# schematic.net
KiCad netlist of a schematic drawn in Altium Designer
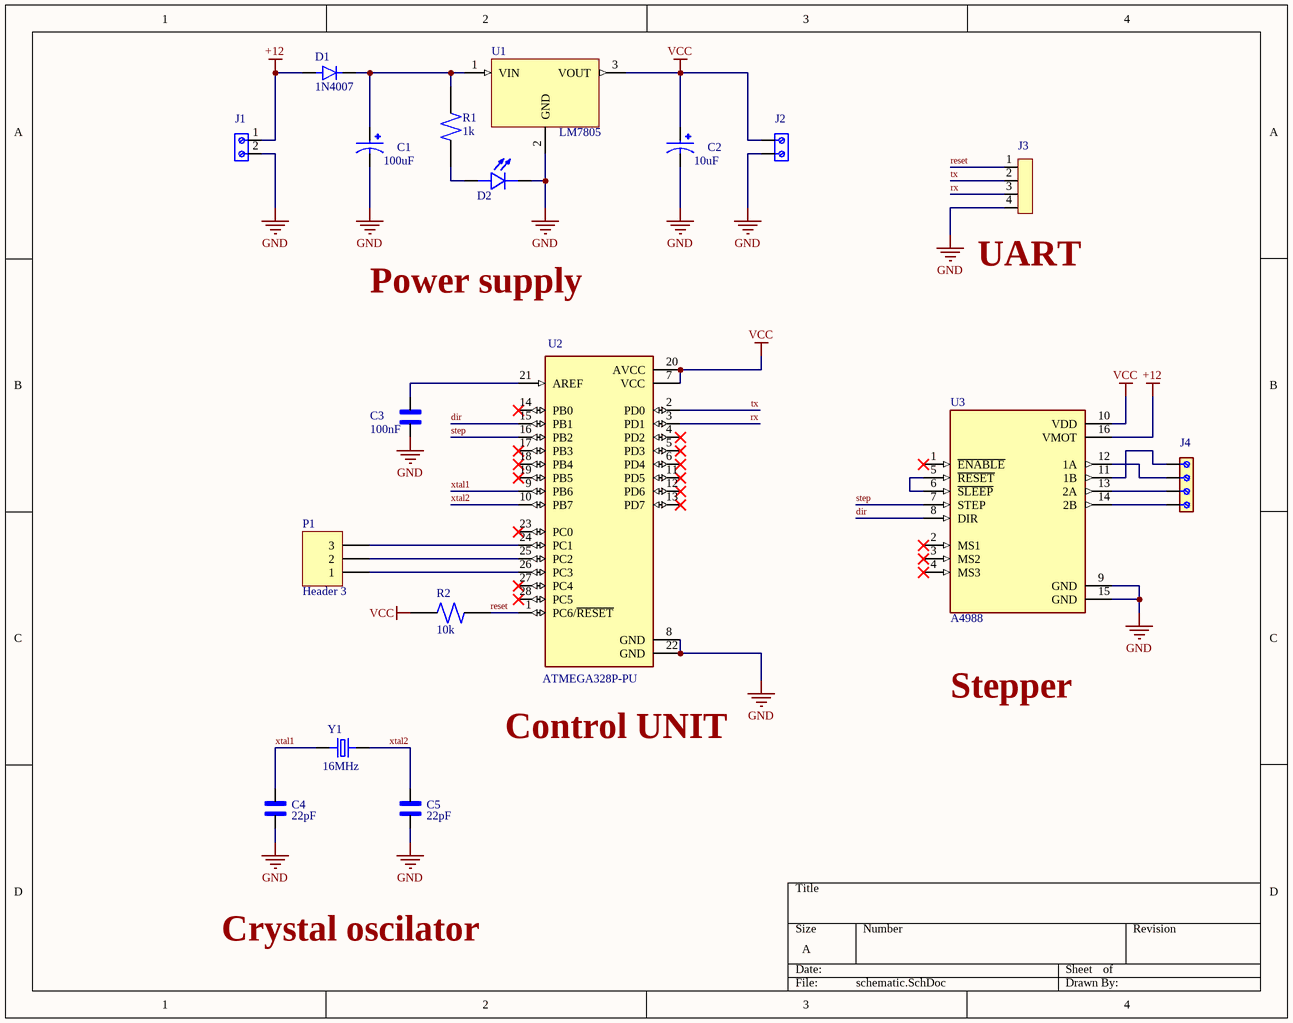
[diagram p0: schematic.SchDoc]

(export (version "E")
  (design (tool "Eeschema 10.0.6"))
  (components
    (comp (ref "C1")
      (value "100uF")
      (footprint "CAPPRD500W50D500H1100")
      (description "FS-A")
      (fields (field (name "MF") "{'manufacturer': u'Panasonic'}") (field (name "MP") "EEUFS0J221B"))
      (libsource (lib "Installed library") (part "Electrolytic capacitor"))
    )
    (comp (ref "C2")
      (value "10uF")
      (footprint "CAPPRD500W50D500H1100")
      (description "FS-A")
      (fields (field (name "MF") "{'manufacturer': u'Panasonic'}") (field (name "MP") "EEUFS0J221B"))
      (libsource (lib "Installed library") (part "Electrolytic capacitor"))
    )
    (comp (ref "C3")
      (value "100nF")
      (footprint "CAPRB500W50L450T300H550")
      (description "2200 pF Â±10% 250V Ceramic Capacitor X7R Radial")
      (fields (field (name "DIGI-KEY_PART_NUMBER") "445-173386-1-ND") (field (name "MF") "TDK"))
      (libsource (lib "Installed library") (part "Ceramic capacitor"))
    )
    (comp (ref "C4")
      (value "22pF")
      (footprint "CAPRB500W50L450T300H550")
      (description "2200 pF Â±10% 250V Ceramic Capacitor X7R Radial")
      (fields (field (name "DIGI-KEY_PART_NUMBER") "445-173386-1-ND") (field (name "MF") "TDK"))
      (libsource (lib "Installed library") (part "Ceramic capacitor"))
    )
    (comp (ref "C5")
      (value "22pF")
      (footprint "CAPRB500W50L450T300H550")
      (description "2200 pF Â±10% 250V Ceramic Capacitor X7R Radial")
      (fields (field (name "DIGI-KEY_PART_NUMBER") "445-173386-1-ND") (field (name "MF") "TDK"))
      (libsource (lib "Installed library") (part "Ceramic capacitor"))
    )
    (comp (ref "D1")
      (value "1N4007")
      (footprint "DIOAD1060W80L520D270")
      (description "Diode Switching 1KV 1A 2-Pin DO-41")
      (libsource (lib "Components") (part "1N4007"))
    )
    (comp (ref "D2")
      (value "L08R5000Q1")
      (footprint "LEDRD254W57D500H1070")
      (description "LED, Orange, Through Hole, T-1 3/4 (5mm), 30 mA, 2.1 V, 635 nm")
      (fields (field (name "MF") "{'manufacturer': u'LED Technology'}"))
      (libsource (lib "Installed library") (part "LED"))
    )
    (comp (ref "J1")
      (value "691111710002")
      (footprint "691111710002")
      (description "2 Position Wire to Board Terminal Block Horizontal with Board 0.197 _5.00mm_ Through Hole")
      (fields (field (name "MF") "Wurth Electronics"))
      (libsource (lib "Installed library") (part "Terminal Block - 2Pins"))
    )
    (comp (ref "J2")
      (value "691111710002")
      (footprint "691111710002")
      (description "2 Position Wire to Board Terminal Block Horizontal with Board 0.197 _5.00mm_ Through Hole")
      (fields (field (name "MF") "Wurth Electronics"))
      (libsource (lib "") (part "Terminal Block - 2Pins_1"))
    )
    (comp (ref "J3")
      (value "PPTC041LFBN-RC")
      (footprint "SULLINS_PPTC041LFBN-RC")
      (description "4 Position Header Connector Through Hole")
      (fields (field (name "MF") "Sullins Connector"))
      (libsource (lib "Installed library") (part "Female header - 4Pins"))
    )
    (comp (ref "J4")
      (value "691241510004")
      (footprint "691241510004")
      (fields (field (name "MF") "WÃ¼rth Elektronik"))
      (libsource (lib "Installed library") (part "Terminal block - 4Pins"))
    )
    (comp (ref "P1")
      (value "Header 3")
      (footprint "HDR1X3")
      (description "Header, 3-Pin")
      (fields (field (name "PUBLISHER") "Altium Limited"))
      (libsource (lib "Miscellaneous Connectors") (part "Header 3"))
    )
    (comp (ref "R1")
      (value "1k")
      (footprint "RESAD1100W55L680D260")
      (description "(MFR-25FBF52-10K) 10,2 kOhm bei 1% 0,25W, 1/4W Durchbohrlochwiderstand Axial Metal Film")
      (fields (field (name "DIGI-KEY_PART_NUMBER") "10.2KXBK-ND") (field (name "MF") "Yageo"))
      (libsource (lib "Installed library") (part "Resistor (0.25W)"))
    )
    (comp (ref "R2")
      (value "10k")
      (footprint "RESAD1100W55L680D260")
      (description "(MFR-25FBF52-10K) 10,2 kOhm bei 1% 0,25W, 1/4W Durchbohrlochwiderstand Axial Metal Film")
      (fields (field (name "DIGI-KEY_PART_NUMBER") "10.2KXBK-ND") (field (name "MF") "Yageo"))
      (libsource (lib "Installed library") (part "Resistor (0.25W)"))
    )
    (comp (ref "U1")
      (value "LM7805")
      (footprint "TO255P1020X450X1968-3")
      (fields (field (name "MP") "LM7805CT/NOPB"))
      (libsource (lib "Voltage regulator") (part "LM78__"))
    )
    (comp (ref "U2")
      (value "ATMEGA328P-PU")
      (footprint "DIP794W46P254L2967H457Q28B")
      (description "ATmega Series 20 MHz 32 KB Flash 2 KB SRAM 8-Bit Microcontroller - DIP-28")
      (libsource (lib "Installed library") (part "ATMEGA328P-PU"))
    )
    (comp (ref "U3")
      (value "A4988")
      (footprint "MODULE_A4988_STEPPER_MOTOR_DRIVER_CARRIER")
      (description "Stepper motor controler; IC: A4988; 1A; Uin mot: 8Ã·35V")
      (fields (field (name "MP") "A4988_STEPPER_MOTOR_DRIVER_CARRIER"))
      (libsource (lib "Modules") (part "A4988_STEPPER_MOTOR_DRIVER_CARRIER"))
    )
    (comp (ref "Y1")
      (value "16MHz")
      (footprint "XTAL_ECS-160-20-4X")
      (description "CRYSTAL T/H")
      (fields (field (name "MF") "{'manufacturer': u'ECS Inc.'}") (field (name "MP") "ECS-160-S-4"))
      (libsource (lib "Installed library") (part "Crystal oscilator"))
    )
  )
  (nets
    (net (code "1") (name "+12") (class "Default")
      (node (ref "D1") (pin "A") (pinfunction "A_A") (pintype "passive"))
      (node (ref "J1") (pin "1") (pinfunction "1_1") (pintype "passive"))
      (node (ref "U3") (pin "16") (pinfunction "VMOT_16") (pintype "power_in"))
    )
    (net (code "2") (name "/dir") (class "Default")
      (node (ref "U2") (pin "15") (pinfunction "PB1_15") (pintype "bidirectional"))
      (node (ref "U3") (pin "8") (pinfunction "DIR_8") (pintype "input"))
    )
    (net (code "3") (name "/reset") (class "Default")
      (node (ref "J3") (pin "1") (pinfunction "1_1") (pintype "passive"))
      (node (ref "R2") (pin "2") (pinfunction "2_2") (pintype "passive"))
      (node (ref "U2") (pin "1") (pinfunction "PC6/~{RESET}_1") (pintype "bidirectional"))
    )
    (net (code "4") (name "/rx") (class "Default")
      (node (ref "J3") (pin "3") (pinfunction "3_3") (pintype "passive"))
      (node (ref "U2") (pin "3") (pinfunction "PD1_3") (pintype "bidirectional"))
    )
    (net (code "5") (name "/step") (class "Default")
      (node (ref "U2") (pin "16") (pinfunction "PB2_16") (pintype "bidirectional"))
      (node (ref "U3") (pin "7") (pinfunction "STEP_7") (pintype "input"))
    )
    (net (code "6") (name "/tx") (class "Default")
      (node (ref "J3") (pin "2") (pinfunction "2_2") (pintype "passive"))
      (node (ref "U2") (pin "2") (pinfunction "PD0_2") (pintype "bidirectional"))
    )
    (net (code "7") (name "/xtal1") (class "Default")
      (node (ref "C4") (pin "1") (pinfunction "1_1") (pintype "passive"))
      (node (ref "U2") (pin "9") (pinfunction "PB6_9") (pintype "bidirectional"))
      (node (ref "Y1") (pin "1") (pinfunction "1_1") (pintype "passive"))
    )
    (net (code "8") (name "/xtal2") (class "Default")
      (node (ref "C5") (pin "1") (pinfunction "1_1") (pintype "passive"))
      (node (ref "U2") (pin "10") (pinfunction "PB7_10") (pintype "bidirectional"))
      (node (ref "Y1") (pin "2") (pinfunction "2_2") (pintype "passive"))
    )
    (net (code "9") (name "GND") (class "Default")
      (node (ref "C1") (pin "N") (pinfunction "N_N") (pintype "passive"))
      (node (ref "C2") (pin "N") (pinfunction "N_N") (pintype "passive"))
      (node (ref "C3") (pin "2") (pinfunction "2_2") (pintype "passive"))
      (node (ref "C4") (pin "2") (pinfunction "2_2") (pintype "passive"))
      (node (ref "C5") (pin "2") (pinfunction "2_2") (pintype "passive"))
      (node (ref "D2") (pin "C") (pinfunction "C_C") (pintype "passive"))
      (node (ref "J1") (pin "2") (pinfunction "2_2") (pintype "passive"))
      (node (ref "J2") (pin "1") (pinfunction "1_1") (pintype "passive"))
      (node (ref "J3") (pin "4") (pinfunction "4_4") (pintype "passive"))
      (node (ref "U1") (pin "2") (pinfunction "GND_2") (pintype "passive"))
      (node (ref "U2") (pin "22") (pinfunction "GND_22") (pintype "power_in"))
      (node (ref "U2") (pin "8") (pinfunction "GND_8") (pintype "power_in"))
      (node (ref "U3") (pin "15") (pinfunction "GND_15") (pintype "power_in"))
      (node (ref "U3") (pin "9") (pinfunction "GND_9") (pintype "power_in"))
    )
    (net (code "10") (name "Net-(D2-PadA)") (class "Default")
      (node (ref "D2") (pin "A") (pinfunction "A_A") (pintype "passive"))
      (node (ref "R1") (pin "2") (pinfunction "2_2") (pintype "passive"))
    )
    (net (code "11") (name "Net-(U1-VIN)") (class "Default")
      (node (ref "C1") (pin "P") (pinfunction "P_P") (pintype "passive"))
      (node (ref "D1") (pin "C") (pinfunction "C_C") (pintype "passive"))
      (node (ref "R1") (pin "1") (pinfunction "1_1") (pintype "passive"))
      (node (ref "U1") (pin "1") (pinfunction "VIN_1") (pintype "input"))
    )
    (net (code "12") (name "Net-(U2-AREF)") (class "Default")
      (node (ref "C3") (pin "1") (pinfunction "1_1") (pintype "passive"))
      (node (ref "U2") (pin "21") (pinfunction "AREF_21") (pintype "input"))
    )
    (net (code "13") (name "Net-(U2-PC1)") (class "Default")
      (node (ref "P1") (pin "3") (pinfunction "3_3") (pintype "passive"))
      (node (ref "U2") (pin "24") (pinfunction "PC1_24") (pintype "bidirectional"))
    )
    (net (code "14") (name "Net-(U2-PC2)") (class "Default")
      (node (ref "P1") (pin "2") (pinfunction "2_2") (pintype "passive"))
      (node (ref "U2") (pin "25") (pinfunction "PC2_25") (pintype "bidirectional"))
    )
    (net (code "15") (name "Net-(U2-PC3)") (class "Default")
      (node (ref "P1") (pin "1") (pinfunction "1_1") (pintype "passive"))
      (node (ref "U2") (pin "26") (pinfunction "PC3_26") (pintype "bidirectional"))
    )
    (net (code "16") (name "Net-(U3-1A)") (class "Default")
      (node (ref "J4") (pin "2") (pinfunction "2_2") (pintype "passive"))
      (node (ref "U3") (pin "12") (pinfunction "1A_12") (pintype "output"))
    )
    (net (code "17") (name "Net-(U3-1B)") (class "Default")
      (node (ref "J4") (pin "1") (pinfunction "1_1") (pintype "passive"))
      (node (ref "U3") (pin "11") (pinfunction "1B_11") (pintype "output"))
    )
    (net (code "18") (name "Net-(U3-2A)") (class "Default")
      (node (ref "J4") (pin "3") (pinfunction "3_3") (pintype "passive"))
      (node (ref "U3") (pin "13") (pinfunction "2A_13") (pintype "output"))
    )
    (net (code "19") (name "Net-(U3-2B)") (class "Default")
      (node (ref "J4") (pin "4") (pinfunction "4_4") (pintype "passive"))
      (node (ref "U3") (pin "14") (pinfunction "2B_14") (pintype "output"))
    )
    (net (code "20") (name "Net-(U3-~{RESET})") (class "Default")
      (node (ref "U3") (pin "5") (pinfunction "~{RESET}_5") (pintype "input"))
      (node (ref "U3") (pin "6") (pinfunction "~{SLEEP}_6") (pintype "input"))
    )
    (net (code "21") (name "VCC") (class "Default")
      (node (ref "C2") (pin "P") (pinfunction "P_P") (pintype "passive"))
      (node (ref "J2") (pin "2") (pinfunction "2_2") (pintype "passive"))
      (node (ref "R2") (pin "1") (pinfunction "1_1") (pintype "passive"))
      (node (ref "U1") (pin "3") (pinfunction "VOUT_3") (pintype "output"))
      (node (ref "U2") (pin "20") (pinfunction "AVCC_20") (pintype "power_in"))
      (node (ref "U2") (pin "7") (pinfunction "VCC_7") (pintype "power_in"))
      (node (ref "U3") (pin "10") (pinfunction "VDD_10") (pintype "power_in"))
    )
    (net (code "22") (name "unconnected-(U2-PB0-Pad14)") (class "Default")
      (node (ref "U2") (pin "14") (pinfunction "PB0_14") (pintype "bidirectional+no_connect"))
    )
    (net (code "23") (name "unconnected-(U2-PB3-Pad17)") (class "Default")
      (node (ref "U2") (pin "17") (pinfunction "PB3_17") (pintype "bidirectional+no_connect"))
    )
    (net (code "24") (name "unconnected-(U2-PB4-Pad18)") (class "Default")
      (node (ref "U2") (pin "18") (pinfunction "PB4_18") (pintype "bidirectional+no_connect"))
    )
    (net (code "25") (name "unconnected-(U2-PB5-Pad19)") (class "Default")
      (node (ref "U2") (pin "19") (pinfunction "PB5_19") (pintype "bidirectional+no_connect"))
    )
    (net (code "26") (name "unconnected-(U2-PC0-Pad23)") (class "Default")
      (node (ref "U2") (pin "23") (pinfunction "PC0_23") (pintype "bidirectional+no_connect"))
    )
    (net (code "27") (name "unconnected-(U2-PC4-Pad27)") (class "Default")
      (node (ref "U2") (pin "27") (pinfunction "PC4_27") (pintype "bidirectional+no_connect"))
    )
    (net (code "28") (name "unconnected-(U2-PC5-Pad28)") (class "Default")
      (node (ref "U2") (pin "28") (pinfunction "PC5_28") (pintype "bidirectional+no_connect"))
    )
    (net (code "29") (name "unconnected-(U2-PD2-Pad4)") (class "Default")
      (node (ref "U2") (pin "4") (pinfunction "PD2_4") (pintype "bidirectional+no_connect"))
    )
    (net (code "30") (name "unconnected-(U2-PD3-Pad5)") (class "Default")
      (node (ref "U2") (pin "5") (pinfunction "PD3_5") (pintype "bidirectional+no_connect"))
    )
    (net (code "31") (name "unconnected-(U2-PD4-Pad6)") (class "Default")
      (node (ref "U2") (pin "6") (pinfunction "PD4_6") (pintype "bidirectional+no_connect"))
    )
    (net (code "32") (name "unconnected-(U2-PD5-Pad11)") (class "Default")
      (node (ref "U2") (pin "11") (pinfunction "PD5_11") (pintype "bidirectional+no_connect"))
    )
    (net (code "33") (name "unconnected-(U2-PD6-Pad12)") (class "Default")
      (node (ref "U2") (pin "12") (pinfunction "PD6_12") (pintype "bidirectional+no_connect"))
    )
    (net (code "34") (name "unconnected-(U2-PD7-Pad13)") (class "Default")
      (node (ref "U2") (pin "13") (pinfunction "PD7_13") (pintype "bidirectional+no_connect"))
    )
    (net (code "35") (name "unconnected-(U3-MS1-Pad2)") (class "Default")
      (node (ref "U3") (pin "2") (pinfunction "MS1_2") (pintype "input+no_connect"))
    )
    (net (code "36") (name "unconnected-(U3-MS2-Pad3)") (class "Default")
      (node (ref "U3") (pin "3") (pinfunction "MS2_3") (pintype "input+no_connect"))
    )
    (net (code "37") (name "unconnected-(U3-MS3-Pad4)") (class "Default")
      (node (ref "U3") (pin "4") (pinfunction "MS3_4") (pintype "input+no_connect"))
    )
    (net (code "38") (name "unconnected-(U3-~{ENABLE}-Pad1)") (class "Default")
      (node (ref "U3") (pin "1") (pinfunction "~{ENABLE}_1") (pintype "input+no_connect"))
    )
  )
)
